# DualBalancedOutput.net
KiCad netlist of a schematic drawn in EAGLE
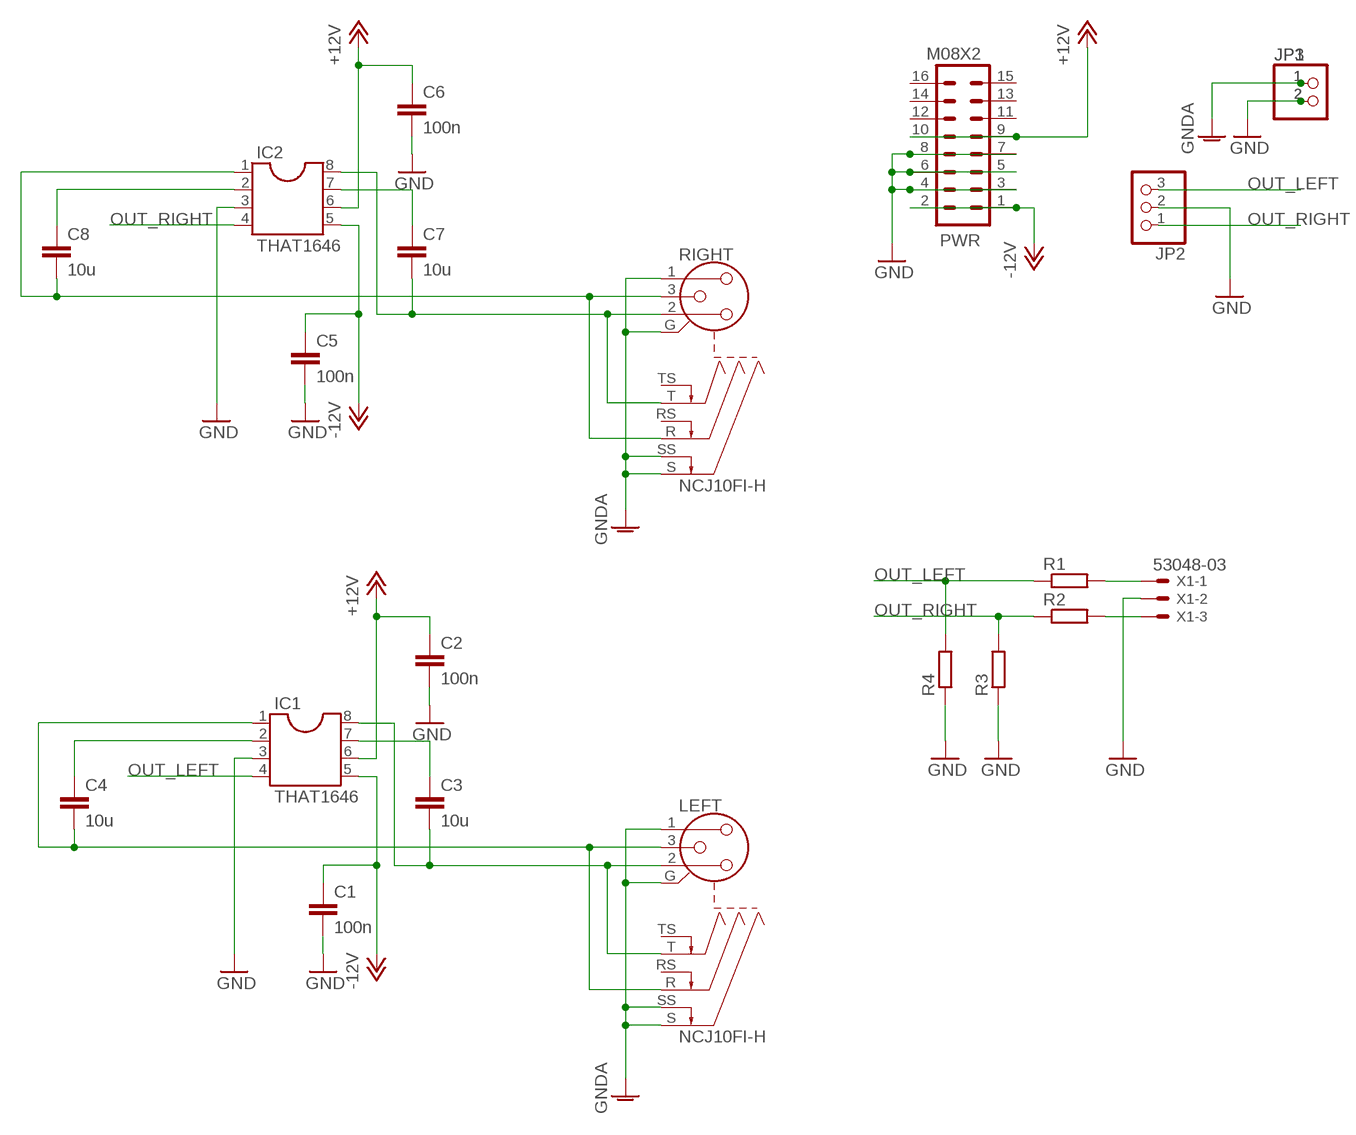
[diagram p0: schematic, sheet 1]

(export (version "E")
  (design (tool "Eeschema 10.0.6"))
  (components
    (comp (ref "C1")
      (value "100n")
      (footprint "eagle-import:C050-025X075")
      (libsource (lib "eagle-import") (part "C-EU050-025X075"))
    )
    (comp (ref "C2")
      (value "100n")
      (footprint "eagle-import:C050-025X075")
      (libsource (lib "eagle-import") (part "C-EU050-025X075"))
    )
    (comp (ref "C3")
      (value "10u")
      (footprint "eagle-import:C050-025X075")
      (libsource (lib "eagle-import") (part "C-EU050-025X075"))
    )
    (comp (ref "C4")
      (value "10u")
      (footprint "eagle-import:C050-025X075")
      (libsource (lib "eagle-import") (part "C-EU050-025X075"))
    )
    (comp (ref "C5")
      (value "100n")
      (footprint "eagle-import:C050-025X075")
      (libsource (lib "eagle-import") (part "C-EU050-025X075"))
    )
    (comp (ref "C6")
      (value "100n")
      (footprint "eagle-import:C050-025X075")
      (libsource (lib "eagle-import") (part "C-EU050-025X075"))
    )
    (comp (ref "C7")
      (value "10u")
      (footprint "eagle-import:C050-025X075")
      (libsource (lib "eagle-import") (part "C-EU050-025X075"))
    )
    (comp (ref "C8")
      (value "10u")
      (footprint "eagle-import:C050-025X075")
      (libsource (lib "eagle-import") (part "C-EU050-025X075"))
    )
    (comp (ref "IC1")
      (value "THAT1646")
      (footprint "eagle-import:DIL08")
      (libsource (lib "eagle-import") (part "DIL8"))
    )
    (comp (ref "IC2")
      (value "THAT1646")
      (footprint "eagle-import:DIL08")
      (libsource (lib "eagle-import") (part "DIL8"))
    )
    (comp (ref "JP1")
      (value "PINHD-1X2")
      (footprint "eagle-import:1X02")
      (libsource (lib "eagle-import") (part "PINHD-1X2"))
    )
    (comp (ref "JP2")
      (value "PINHD-1X3")
      (footprint "eagle-import:1X03")
      (libsource (lib "eagle-import") (part "PINHD-1X3"))
    )
    (comp (ref "JP3")
      (value "PINHD-1X2")
      (footprint "eagle-import:1X02")
      (libsource (lib "eagle-import") (part "PINHD-1X2"))
    )
    (comp (ref "LEFT")
      (value "NCJ10FI-H")
      (footprint "eagle-import:NCJ10FI-H")
      (libsource (lib "eagle-import") (part "NCJ10FI-H"))
    )
    (comp (ref "PWR")
      (value "M08X2")
      (footprint "eagle-import:2X8")
      (libsource (lib "eagle-import") (part "M08X2"))
    )
    (comp (ref "R1")
      (value "R-EU_0207/7")
      (footprint "eagle-import:0207_7")
      (libsource (lib "eagle-import") (part "R-EU_0207/7"))
    )
    (comp (ref "R2")
      (value "R-EU_0207/7")
      (footprint "eagle-import:0207_7")
      (libsource (lib "eagle-import") (part "R-EU_0207/7"))
    )
    (comp (ref "R3")
      (value "R-EU_0207/7")
      (footprint "eagle-import:0207_7")
      (libsource (lib "eagle-import") (part "R-EU_0207/7"))
    )
    (comp (ref "R4")
      (value "R-EU_0207/7")
      (footprint "eagle-import:0207_7")
      (libsource (lib "eagle-import") (part "R-EU_0207/7"))
    )
    (comp (ref "RIGHT")
      (value "NCJ10FI-H")
      (footprint "eagle-import:NCJ10FI-H")
      (libsource (lib "eagle-import") (part "NCJ10FI-H"))
    )
    (comp (ref "X1")
      (value "53048-03")
      (footprint "eagle-import:53048-03")
      (fields (field (name "MF") "WALDOM/MOLEX") (field (name "MPN") "53048-0310"))
      (libsource (lib "eagle-import") (part "53?-03048"))
    )
  )
  (nets
    (net (code "1") (name "+12V") (class "Default")
      (node (ref "C2") (pin "1") (pinfunction "1_1") (pintype "passive"))
      (node (ref "C6") (pin "1") (pinfunction "1_1") (pintype "passive"))
      (node (ref "IC1") (pin "6") (pinfunction "6_6") (pintype "passive"))
      (node (ref "IC2") (pin "6") (pinfunction "6_6") (pintype "passive"))
      (node (ref "PWR") (pin "10") (pinfunction "10_10") (pintype "passive"))
      (node (ref "PWR") (pin "9") (pinfunction "9_9") (pintype "passive"))
    )
    (net (code "2") (name "-12V") (class "Default")
      (node (ref "C1") (pin "1") (pinfunction "1_1") (pintype "passive"))
      (node (ref "C5") (pin "1") (pinfunction "1_1") (pintype "passive"))
      (node (ref "IC1") (pin "5") (pinfunction "5_5") (pintype "passive"))
      (node (ref "IC2") (pin "5") (pinfunction "5_5") (pintype "passive"))
      (node (ref "PWR") (pin "1") (pinfunction "1_1") (pintype "passive"))
      (node (ref "PWR") (pin "2") (pinfunction "2_2") (pintype "passive"))
    )
    (net (code "3") (name "/OUT_LEFT") (class "Default")
      (node (ref "IC1") (pin "4") (pinfunction "4_4") (pintype "passive"))
      (node (ref "JP2") (pin "3") (pinfunction "3_3") (pintype "passive"))
      (node (ref "R1") (pin "1") (pinfunction "1_1") (pintype "passive"))
      (node (ref "R4") (pin "2") (pinfunction "2_2") (pintype "passive"))
    )
    (net (code "4") (name "/OUT_RIGHT") (class "Default")
      (node (ref "IC2") (pin "4") (pinfunction "4_4") (pintype "passive"))
      (node (ref "JP2") (pin "1") (pinfunction "1_1") (pintype "passive"))
      (node (ref "R2") (pin "1") (pinfunction "1_1") (pintype "passive"))
      (node (ref "R3") (pin "2") (pinfunction "2_2") (pintype "passive"))
    )
    (net (code "5") (name "GND") (class "Default")
      (node (ref "C1") (pin "2") (pinfunction "2_2") (pintype "passive"))
      (node (ref "C2") (pin "2") (pinfunction "2_2") (pintype "passive"))
      (node (ref "C5") (pin "2") (pinfunction "2_2") (pintype "passive"))
      (node (ref "C6") (pin "2") (pinfunction "2_2") (pintype "passive"))
      (node (ref "IC1") (pin "3") (pinfunction "3_3") (pintype "passive"))
      (node (ref "IC2") (pin "3") (pinfunction "3_3") (pintype "passive"))
      (node (ref "JP1") (pin "2") (pinfunction "2_2") (pintype "passive"))
      (node (ref "JP2") (pin "2") (pinfunction "2_2") (pintype "passive"))
      (node (ref "JP3") (pin "2") (pinfunction "2_2") (pintype "passive"))
      (node (ref "PWR") (pin "3") (pinfunction "3_3") (pintype "passive"))
      (node (ref "PWR") (pin "4") (pinfunction "4_4") (pintype "passive"))
      (node (ref "PWR") (pin "5") (pinfunction "5_5") (pintype "passive"))
      (node (ref "PWR") (pin "6") (pinfunction "6_6") (pintype "passive"))
      (node (ref "PWR") (pin "7") (pinfunction "7_7") (pintype "passive"))
      (node (ref "PWR") (pin "8") (pinfunction "8_8") (pintype "passive"))
      (node (ref "R3") (pin "1") (pinfunction "1_1") (pintype "passive"))
      (node (ref "R4") (pin "1") (pinfunction "1_1") (pintype "passive"))
      (node (ref "X1") (pin "2") (pinfunction "S_2") (pintype "passive"))
    )
    (net (code "6") (name "GNDA") (class "Default")
      (node (ref "JP1") (pin "1") (pinfunction "1_1") (pintype "passive"))
      (node (ref "JP3") (pin "1") (pinfunction "1_1") (pintype "passive"))
      (node (ref "LEFT") (pin "1") (pinfunction "1_1") (pintype "passive"))
      (node (ref "LEFT") (pin "G") (pinfunction "G_G") (pintype "passive"))
      (node (ref "LEFT") (pin "S") (pinfunction "S_S") (pintype "passive"))
      (node (ref "LEFT") (pin "SS") (pinfunction "SS_SS") (pintype "passive"))
      (node (ref "RIGHT") (pin "1") (pinfunction "1_1") (pintype "passive"))
      (node (ref "RIGHT") (pin "G") (pinfunction "G_G") (pintype "passive"))
      (node (ref "RIGHT") (pin "S") (pinfunction "S_S") (pintype "passive"))
      (node (ref "RIGHT") (pin "SS") (pinfunction "SS_SS") (pintype "passive"))
    )
    (net (code "7") (name "Net-(C3-Pad1)") (class "Default")
      (node (ref "C3") (pin "1") (pinfunction "1_1") (pintype "passive"))
      (node (ref "IC1") (pin "7") (pinfunction "7_7") (pintype "passive"))
    )
    (net (code "8") (name "Net-(C3-Pad2)") (class "Default")
      (node (ref "C3") (pin "2") (pinfunction "2_2") (pintype "passive"))
      (node (ref "IC1") (pin "8") (pinfunction "8_8") (pintype "passive"))
      (node (ref "LEFT") (pin "2") (pinfunction "2_2") (pintype "passive"))
      (node (ref "LEFT") (pin "T") (pinfunction "T_T") (pintype "passive"))
    )
    (net (code "9") (name "Net-(C4-Pad1)") (class "Default")
      (node (ref "C4") (pin "1") (pinfunction "1_1") (pintype "passive"))
      (node (ref "IC1") (pin "2") (pinfunction "2_2") (pintype "passive"))
    )
    (net (code "10") (name "Net-(C4-Pad2)") (class "Default")
      (node (ref "C4") (pin "2") (pinfunction "2_2") (pintype "passive"))
      (node (ref "IC1") (pin "1") (pinfunction "1_1") (pintype "passive"))
      (node (ref "LEFT") (pin "3") (pinfunction "3_3") (pintype "passive"))
      (node (ref "LEFT") (pin "R") (pinfunction "R_R") (pintype "passive"))
    )
    (net (code "11") (name "Net-(C7-Pad1)") (class "Default")
      (node (ref "C7") (pin "1") (pinfunction "1_1") (pintype "passive"))
      (node (ref "IC2") (pin "7") (pinfunction "7_7") (pintype "passive"))
    )
    (net (code "12") (name "Net-(C7-Pad2)") (class "Default")
      (node (ref "C7") (pin "2") (pinfunction "2_2") (pintype "passive"))
      (node (ref "IC2") (pin "8") (pinfunction "8_8") (pintype "passive"))
      (node (ref "RIGHT") (pin "2") (pinfunction "2_2") (pintype "passive"))
      (node (ref "RIGHT") (pin "T") (pinfunction "T_T") (pintype "passive"))
    )
    (net (code "13") (name "Net-(C8-Pad1)") (class "Default")
      (node (ref "C8") (pin "1") (pinfunction "1_1") (pintype "passive"))
      (node (ref "IC2") (pin "2") (pinfunction "2_2") (pintype "passive"))
    )
    (net (code "14") (name "Net-(C8-Pad2)") (class "Default")
      (node (ref "C8") (pin "2") (pinfunction "2_2") (pintype "passive"))
      (node (ref "IC2") (pin "1") (pinfunction "1_1") (pintype "passive"))
      (node (ref "RIGHT") (pin "3") (pinfunction "3_3") (pintype "passive"))
      (node (ref "RIGHT") (pin "R") (pinfunction "R_R") (pintype "passive"))
    )
    (net (code "15") (name "Net-(X1A-S)") (class "Default")
      (node (ref "R1") (pin "2") (pinfunction "2_2") (pintype "passive"))
      (node (ref "X1") (pin "1") (pinfunction "S_1") (pintype "passive"))
    )
    (net (code "16") (name "Net-(X1C-S)") (class "Default")
      (node (ref "R2") (pin "2") (pinfunction "2_2") (pintype "passive"))
      (node (ref "X1") (pin "3") (pinfunction "S_3") (pintype "passive"))
    )
    (net (code "17") (name "unconnected-(LEFT-PadRS)") (class "Default")
      (node (ref "LEFT") (pin "RS") (pinfunction "RS_RS") (pintype "passive"))
    )
    (net (code "18") (name "unconnected-(LEFT-PadTS)") (class "Default")
      (node (ref "LEFT") (pin "TS") (pinfunction "TS_TS") (pintype "passive"))
    )
    (net (code "19") (name "unconnected-(PWR-Pad11)") (class "Default")
      (node (ref "PWR") (pin "11") (pinfunction "11_11") (pintype "passive"))
    )
    (net (code "20") (name "unconnected-(PWR-Pad12)") (class "Default")
      (node (ref "PWR") (pin "12") (pinfunction "12_12") (pintype "passive"))
    )
    (net (code "21") (name "unconnected-(PWR-Pad13)") (class "Default")
      (node (ref "PWR") (pin "13") (pinfunction "13_13") (pintype "passive"))
    )
    (net (code "22") (name "unconnected-(PWR-Pad14)") (class "Default")
      (node (ref "PWR") (pin "14") (pinfunction "14_14") (pintype "passive"))
    )
    (net (code "23") (name "unconnected-(PWR-Pad15)") (class "Default")
      (node (ref "PWR") (pin "15") (pinfunction "15_15") (pintype "passive"))
    )
    (net (code "24") (name "unconnected-(PWR-Pad16)") (class "Default")
      (node (ref "PWR") (pin "16") (pinfunction "16_16") (pintype "passive"))
    )
    (net (code "25") (name "unconnected-(RIGHT-PadRS)") (class "Default")
      (node (ref "RIGHT") (pin "RS") (pinfunction "RS_RS") (pintype "passive"))
    )
    (net (code "26") (name "unconnected-(RIGHT-PadTS)") (class "Default")
      (node (ref "RIGHT") (pin "TS") (pinfunction "TS_TS") (pintype "passive"))
    )
  )
)
